# GasSensorModule_v2_0.net
KiCad netlist of a schematic drawn in EAGLE
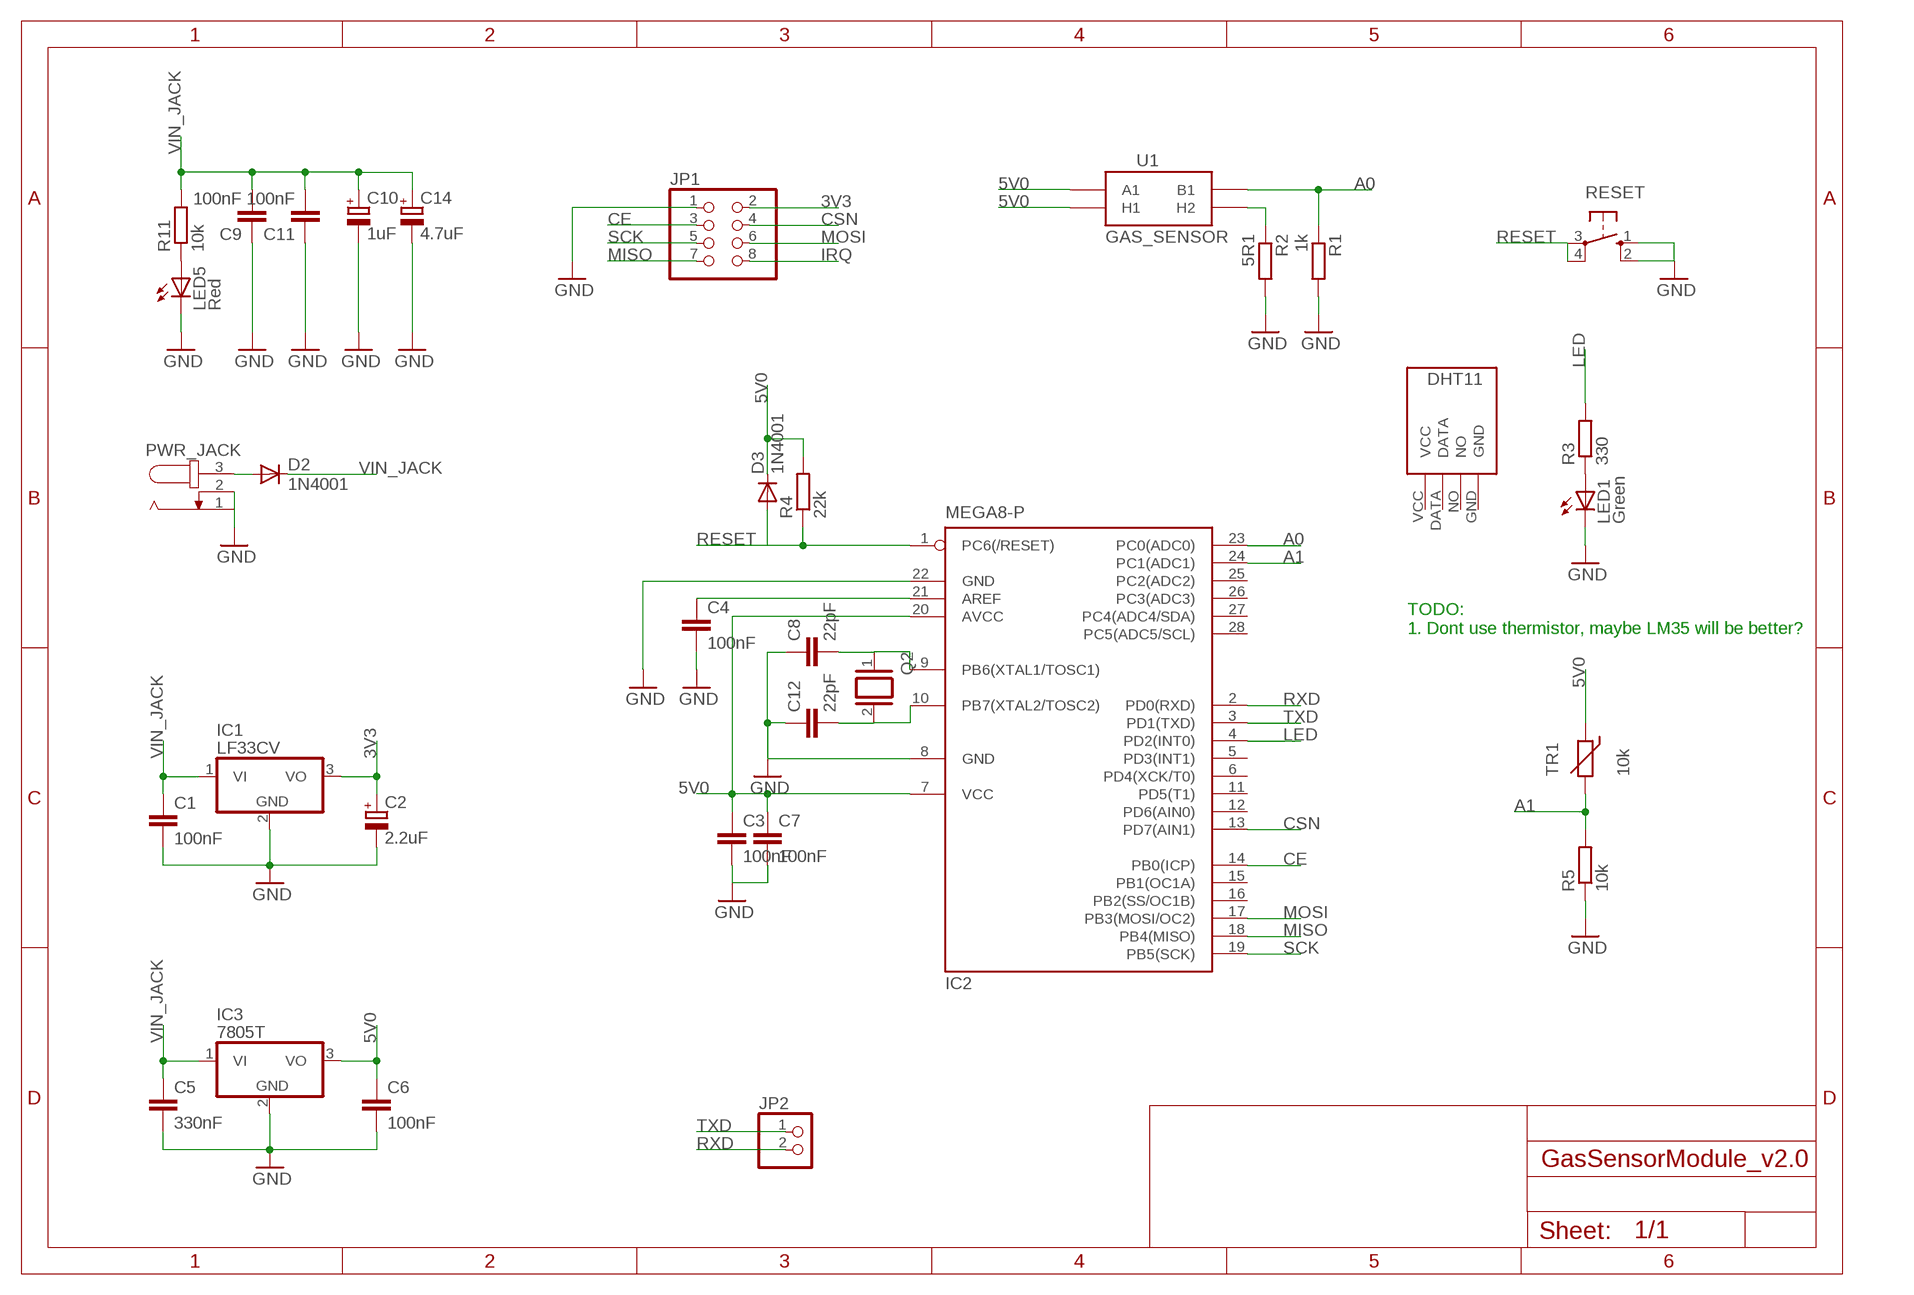
[diagram p0: schematic, sheet 1]

(export (version "E")
  (design (tool "Eeschema 10.0.6"))
  (components
    (comp (ref "C1")
      (value "100nF")
      (footprint "eagle-import:C025-025X050")
      (libsource (lib "eagle-import") (part "C-EU025-025X050"))
    )
    (comp (ref "C2")
      (value "2.2uF")
      (footprint "eagle-import:E2,5-5")
      (libsource (lib "eagle-import") (part "CPOL-EUE2.5-5"))
    )
    (comp (ref "C3")
      (value "100nF")
      (footprint "eagle-import:C025-025X050")
      (libsource (lib "eagle-import") (part "C-EU025-025X050"))
    )
    (comp (ref "C4")
      (value "100nF")
      (footprint "eagle-import:C025-025X050")
      (libsource (lib "eagle-import") (part "C-EU025-025X050"))
    )
    (comp (ref "C5")
      (value "330nF")
      (footprint "eagle-import:C025-025X050")
      (libsource (lib "eagle-import") (part "C-EU025-025X050"))
    )
    (comp (ref "C6")
      (value "100nF")
      (footprint "eagle-import:C025-025X050")
      (libsource (lib "eagle-import") (part "C-EU025-025X050"))
    )
    (comp (ref "C7")
      (value "100nF")
      (footprint "eagle-import:C025-025X050")
      (libsource (lib "eagle-import") (part "C-EU025-025X050"))
    )
    (comp (ref "C8")
      (value "22pF")
      (footprint "eagle-import:C025-025X050")
      (libsource (lib "eagle-import") (part "C-EU025-025X050"))
    )
    (comp (ref "C9")
      (value "100nF")
      (footprint "eagle-import:C025-025X050")
      (libsource (lib "eagle-import") (part "C-EU025-025X050"))
    )
    (comp (ref "C10")
      (value "1uF")
      (footprint "eagle-import:E2,5-5")
      (libsource (lib "eagle-import") (part "CPOL-EUE2.5-5"))
    )
    (comp (ref "C11")
      (value "100nF")
      (footprint "eagle-import:C025-025X050")
      (libsource (lib "eagle-import") (part "C-EU025-025X050"))
    )
    (comp (ref "C12")
      (value "22pF")
      (footprint "eagle-import:C025-025X050")
      (libsource (lib "eagle-import") (part "C-EU025-025X050"))
    )
    (comp (ref "C14")
      (value "4.7uF")
      (footprint "eagle-import:E2,5-5")
      (libsource (lib "eagle-import") (part "CPOL-EUE2.5-5"))
    )
    (comp (ref "D2")
      (value "1N4001")
      (footprint "eagle-import:DO41-10")
      (libsource (lib "eagle-import") (part "1N4004"))
    )
    (comp (ref "D3")
      (value "1N4001")
      (footprint "eagle-import:DO41-10")
      (libsource (lib "eagle-import") (part "1N4004"))
    )
    (comp (ref "IC1")
      (value "LF33CV")
      (footprint "eagle-import:TO220H")
      (libsource (lib "eagle-import") (part "78T05"))
    )
    (comp (ref "IC2")
      (value "MEGA8-P")
      (footprint "eagle-import:DIL28-3")
      (libsource (lib "eagle-import") (part "MEGA8-P"))
    )
    (comp (ref "IC3")
      (value "7805T")
      (footprint "eagle-import:TO220H")
      (libsource (lib "eagle-import") (part "78T05"))
    )
    (comp (ref "JP1")
      (value "PINHD-2X4")
      (footprint "eagle-import:2X04")
      (libsource (lib "eagle-import") (part "PINHD-2X4"))
    )
    (comp (ref "JP2")
      (value "PINHD-1X2/90")
      (footprint "eagle-import:1X02_90")
      (libsource (lib "eagle-import") (part "PINHD-1X2/90"))
    )
    (comp (ref "LED1")
      (value "Green")
      (footprint "eagle-import:LED3MM")
      (libsource (lib "eagle-import") (part "LED3MM"))
    )
    (comp (ref "LED5")
      (value "Red")
      (footprint "eagle-import:LED3MM")
      (libsource (lib "eagle-import") (part "LED3MM"))
    )
    (comp (ref "PWR_JACK")
      (value "JACK-PLUG0")
      (footprint "eagle-import:SPC4077")
      (libsource (lib "eagle-import") (part "JACK-PLUG0"))
    )
    (comp (ref "Q2")
      (value "XTAL/S")
      (footprint "eagle-import:QS")
      (libsource (lib "eagle-import") (part "XTAL/S"))
    )
    (comp (ref "R1")
      (value "1k")
      (footprint "eagle-import:0207_10")
      (libsource (lib "eagle-import") (part "R-EU_0207/10"))
    )
    (comp (ref "R2")
      (value "5R1")
      (footprint "eagle-import:0207_10")
      (libsource (lib "eagle-import") (part "R-EU_0207/10"))
    )
    (comp (ref "R3")
      (value "330")
      (footprint "eagle-import:0207_10")
      (libsource (lib "eagle-import") (part "R-EU_0207/10"))
    )
    (comp (ref "R4")
      (value "22k")
      (footprint "eagle-import:0207_10")
      (libsource (lib "eagle-import") (part "R-EU_0207/10"))
    )
    (comp (ref "R5")
      (value "10k")
      (footprint "eagle-import:0207_10")
      (libsource (lib "eagle-import") (part "R-EU_0207/10"))
    )
    (comp (ref "R11")
      (value "10k")
      (footprint "eagle-import:0207_10")
      (libsource (lib "eagle-import") (part "R-EU_0207/10"))
    )
    (comp (ref "RESET")
      (value "10-XX")
      (footprint "eagle-import:B3F-10XX")
      (fields (field (name "MPN") "B3F-1000"))
      (libsource (lib "eagle-import") (part "10-XX"))
    )
    (comp (ref "TR1")
      (value "10k")
      (footprint "eagle-import:RS-2,5")
      (libsource (lib "eagle-import") (part "THERMISTOR_R-2,5"))
    )
    (comp (ref "U$1")
      (value "DHT11-PION.")
      (footprint "eagle-import:DHT11-PION.")
      (libsource (lib "eagle-import") (part "DHT11-PION."))
    )
    (comp (ref "U1")
      (value "GAS_SENSOR")
      (footprint "eagle-import:MQ-3")
      (libsource (lib "eagle-import") (part "GAS_SENSOR"))
    )
  )
  (nets
    (net (code "1") (name "/3V3") (class "Default")
      (node (ref "C2") (pin "+") (pinfunction "+_+") (pintype "passive"))
      (node (ref "IC1") (pin "3") (pinfunction "VO_3") (pintype "passive"))
      (node (ref "JP1") (pin "2") (pinfunction "2_2") (pintype "passive"))
    )
    (net (code "2") (name "/5V0") (class "Default")
      (node (ref "C3") (pin "1") (pinfunction "1_1") (pintype "passive"))
      (node (ref "C6") (pin "1") (pinfunction "1_1") (pintype "passive"))
      (node (ref "C7") (pin "1") (pinfunction "1_1") (pintype "passive"))
      (node (ref "D3") (pin "C") (pinfunction "C_C") (pintype "passive"))
      (node (ref "IC2") (pin "20") (pinfunction "AVCC_20") (pintype "power_in"))
      (node (ref "IC2") (pin "7") (pinfunction "VCC_7") (pintype "power_in"))
      (node (ref "IC3") (pin "3") (pinfunction "VO_3") (pintype "passive"))
      (node (ref "R4") (pin "2") (pinfunction "2_2") (pintype "passive"))
      (node (ref "TR1") (pin "1") (pinfunction "1_1") (pintype "passive"))
      (node (ref "U1") (pin "A1") (pinfunction "A1_A1") (pintype "bidirectional"))
      (node (ref "U1") (pin "HA") (pinfunction "H1_HA") (pintype "bidirectional"))
    )
    (net (code "3") (name "/A0") (class "Default")
      (node (ref "IC2") (pin "23") (pinfunction "PC0(ADC0)_23") (pintype "bidirectional"))
      (node (ref "R1") (pin "1") (pinfunction "1_1") (pintype "passive"))
      (node (ref "U1") (pin "B1") (pinfunction "B1_B1") (pintype "bidirectional"))
    )
    (net (code "4") (name "/A1") (class "Default")
      (node (ref "IC2") (pin "24") (pinfunction "PC1(ADC1)_24") (pintype "bidirectional"))
      (node (ref "R5") (pin "2") (pinfunction "2_2") (pintype "passive"))
      (node (ref "TR1") (pin "2") (pinfunction "2_2") (pintype "passive"))
    )
    (net (code "5") (name "/CE") (class "Default")
      (node (ref "IC2") (pin "14") (pinfunction "PB0(ICP)_14") (pintype "bidirectional"))
      (node (ref "JP1") (pin "3") (pinfunction "3_3") (pintype "passive"))
    )
    (net (code "6") (name "/CSN") (class "Default")
      (node (ref "IC2") (pin "13") (pinfunction "PD7(AIN1)_13") (pintype "bidirectional"))
      (node (ref "JP1") (pin "4") (pinfunction "4_4") (pintype "passive"))
    )
    (net (code "7") (name "/IRQ") (class "Default")
      (node (ref "JP1") (pin "8") (pinfunction "8_8") (pintype "passive"))
    )
    (net (code "8") (name "/LED") (class "Default")
      (node (ref "IC2") (pin "4") (pinfunction "PD2(INT0)_4") (pintype "bidirectional"))
      (node (ref "R3") (pin "2") (pinfunction "2_2") (pintype "passive"))
    )
    (net (code "9") (name "/MISO") (class "Default")
      (node (ref "IC2") (pin "18") (pinfunction "PB4(MISO)_18") (pintype "bidirectional"))
      (node (ref "JP1") (pin "7") (pinfunction "7_7") (pintype "passive"))
    )
    (net (code "10") (name "/MOSI") (class "Default")
      (node (ref "IC2") (pin "17") (pinfunction "PB3(MOSI/OC2)_17") (pintype "bidirectional"))
      (node (ref "JP1") (pin "6") (pinfunction "6_6") (pintype "passive"))
    )
    (net (code "11") (name "/RESET") (class "Default")
      (node (ref "D3") (pin "A") (pinfunction "A_A") (pintype "passive"))
      (node (ref "IC2") (pin "1") (pinfunction "PC6(/RESET)_1") (pintype "bidirectional"))
      (node (ref "R4") (pin "1") (pinfunction "1_1") (pintype "passive"))
      (node (ref "RESET") (pin "3") (pinfunction "P_3") (pintype "passive"))
      (node (ref "RESET") (pin "4") (pinfunction "P1_4") (pintype "passive"))
    )
    (net (code "12") (name "/RXD") (class "Default")
      (node (ref "IC2") (pin "2") (pinfunction "PD0(RXD)_2") (pintype "bidirectional"))
      (node (ref "JP2") (pin "2") (pinfunction "2_2") (pintype "passive"))
    )
    (net (code "13") (name "/SCK") (class "Default")
      (node (ref "IC2") (pin "19") (pinfunction "PB5(SCK)_19") (pintype "bidirectional"))
      (node (ref "JP1") (pin "5") (pinfunction "5_5") (pintype "passive"))
    )
    (net (code "14") (name "/TXD") (class "Default")
      (node (ref "IC2") (pin "3") (pinfunction "PD1(TXD)_3") (pintype "bidirectional"))
      (node (ref "JP2") (pin "1") (pinfunction "1_1") (pintype "passive"))
    )
    (net (code "15") (name "/VIN_JACK") (class "Default")
      (node (ref "C1") (pin "1") (pinfunction "1_1") (pintype "passive"))
      (node (ref "C10") (pin "+") (pinfunction "+_+") (pintype "passive"))
      (node (ref "C11") (pin "2") (pinfunction "2_2") (pintype "passive"))
      (node (ref "C14") (pin "+") (pinfunction "+_+") (pintype "passive"))
      (node (ref "C5") (pin "1") (pinfunction "1_1") (pintype "passive"))
      (node (ref "C9") (pin "2") (pinfunction "2_2") (pintype "passive"))
      (node (ref "D2") (pin "C") (pinfunction "C_C") (pintype "passive"))
      (node (ref "IC1") (pin "1") (pinfunction "VI_1") (pintype "input"))
      (node (ref "IC3") (pin "1") (pinfunction "VI_1") (pintype "input"))
      (node (ref "R11") (pin "2") (pinfunction "2_2") (pintype "passive"))
    )
    (net (code "16") (name "GND") (class "Default")
      (node (ref "C1") (pin "2") (pinfunction "2_2") (pintype "passive"))
      (node (ref "C10") (pin "-") (pinfunction "-_-") (pintype "passive"))
      (node (ref "C11") (pin "1") (pinfunction "1_1") (pintype "passive"))
      (node (ref "C12") (pin "1") (pinfunction "1_1") (pintype "passive"))
      (node (ref "C14") (pin "-") (pinfunction "-_-") (pintype "passive"))
      (node (ref "C2") (pin "-") (pinfunction "-_-") (pintype "passive"))
      (node (ref "C3") (pin "2") (pinfunction "2_2") (pintype "passive"))
      (node (ref "C4") (pin "2") (pinfunction "2_2") (pintype "passive"))
      (node (ref "C5") (pin "2") (pinfunction "2_2") (pintype "passive"))
      (node (ref "C6") (pin "2") (pinfunction "2_2") (pintype "passive"))
      (node (ref "C7") (pin "2") (pinfunction "2_2") (pintype "passive"))
      (node (ref "C8") (pin "1") (pinfunction "1_1") (pintype "passive"))
      (node (ref "C9") (pin "1") (pinfunction "1_1") (pintype "passive"))
      (node (ref "IC1") (pin "2") (pinfunction "GND_2") (pintype "passive"))
      (node (ref "IC2") (pin "22") (pinfunction "GND_22") (pintype "power_in"))
      (node (ref "IC2") (pin "8") (pinfunction "GND_8") (pintype "power_in"))
      (node (ref "IC3") (pin "2") (pinfunction "GND_2") (pintype "passive"))
      (node (ref "JP1") (pin "1") (pinfunction "1_1") (pintype "passive"))
      (node (ref "LED1") (pin "K") (pinfunction "C_K") (pintype "passive"))
      (node (ref "LED5") (pin "K") (pinfunction "C_K") (pintype "passive"))
      (node (ref "PWR_JACK") (pin "1") (pinfunction "1_1") (pintype "passive"))
      (node (ref "PWR_JACK") (pin "2") (pinfunction "2_2") (pintype "passive"))
      (node (ref "R1") (pin "2") (pinfunction "2_2") (pintype "passive"))
      (node (ref "R2") (pin "2") (pinfunction "2_2") (pintype "passive"))
      (node (ref "R5") (pin "1") (pinfunction "1_1") (pintype "passive"))
      (node (ref "RESET") (pin "1") (pinfunction "S_1") (pintype "passive"))
      (node (ref "RESET") (pin "2") (pinfunction "S1_2") (pintype "passive"))
    )
    (net (code "17") (name "Net-(D2-PadA)") (class "Default")
      (node (ref "D2") (pin "A") (pinfunction "A_A") (pintype "passive"))
      (node (ref "PWR_JACK") (pin "3") (pinfunction "3_3") (pintype "passive"))
    )
    (net (code "18") (name "Net-(IC2-AREF)") (class "Default")
      (node (ref "C4") (pin "1") (pinfunction "1_1") (pintype "passive"))
      (node (ref "IC2") (pin "21") (pinfunction "AREF_21") (pintype "passive"))
    )
    (net (code "19") (name "Net-(IC2-PB6(XTAL1{slash}TOSC1))") (class "Default")
      (node (ref "C8") (pin "2") (pinfunction "2_2") (pintype "passive"))
      (node (ref "IC2") (pin "9") (pinfunction "PB6(XTAL1/TOSC1)_9") (pintype "bidirectional"))
      (node (ref "Q2") (pin "1") (pinfunction "1_1") (pintype "passive"))
    )
    (net (code "20") (name "Net-(IC2-PB7(XTAL2{slash}TOSC2))") (class "Default")
      (node (ref "C12") (pin "2") (pinfunction "2_2") (pintype "passive"))
      (node (ref "IC2") (pin "10") (pinfunction "PB7(XTAL2/TOSC2)_10") (pintype "bidirectional"))
      (node (ref "Q2") (pin "2") (pinfunction "2_2") (pintype "passive"))
    )
    (net (code "21") (name "Net-(LED1-PadA)") (class "Default")
      (node (ref "LED1") (pin "A") (pinfunction "A_A") (pintype "passive"))
      (node (ref "R3") (pin "1") (pinfunction "1_1") (pintype "passive"))
    )
    (net (code "22") (name "Net-(LED5-PadA)") (class "Default")
      (node (ref "LED5") (pin "A") (pinfunction "A_A") (pintype "passive"))
      (node (ref "R11") (pin "1") (pinfunction "1_1") (pintype "passive"))
    )
    (net (code "23") (name "Net-(U1-H2)") (class "Default")
      (node (ref "R2") (pin "1") (pinfunction "1_1") (pintype "passive"))
      (node (ref "U1") (pin "HB") (pinfunction "H2_HB") (pintype "bidirectional"))
    )
    (net (code "24") (name "unconnected-(IC2-PB1(OC1A)-Pad15)") (class "Default")
      (node (ref "IC2") (pin "15") (pinfunction "PB1(OC1A)_15") (pintype "bidirectional"))
    )
    (net (code "25") (name "unconnected-(IC2-PB2(SS{slash}OC1B)-Pad16)") (class "Default")
      (node (ref "IC2") (pin "16") (pinfunction "PB2(SS/OC1B)_16") (pintype "bidirectional"))
    )
    (net (code "26") (name "unconnected-(IC2-PC2(ADC2)-Pad25)") (class "Default")
      (node (ref "IC2") (pin "25") (pinfunction "PC2(ADC2)_25") (pintype "bidirectional"))
    )
    (net (code "27") (name "unconnected-(IC2-PC3(ADC3)-Pad26)") (class "Default")
      (node (ref "IC2") (pin "26") (pinfunction "PC3(ADC3)_26") (pintype "bidirectional"))
    )
    (net (code "28") (name "unconnected-(IC2-PC4(ADC4{slash}SDA)-Pad27)") (class "Default")
      (node (ref "IC2") (pin "27") (pinfunction "PC4(ADC4/SDA)_27") (pintype "bidirectional"))
    )
    (net (code "29") (name "unconnected-(IC2-PC5(ADC5{slash}SCL)-Pad28)") (class "Default")
      (node (ref "IC2") (pin "28") (pinfunction "PC5(ADC5/SCL)_28") (pintype "bidirectional"))
    )
    (net (code "30") (name "unconnected-(IC2-PD3(INT1)-Pad5)") (class "Default")
      (node (ref "IC2") (pin "5") (pinfunction "PD3(INT1)_5") (pintype "bidirectional"))
    )
    (net (code "31") (name "unconnected-(IC2-PD4(XCK{slash}T0)-Pad6)") (class "Default")
      (node (ref "IC2") (pin "6") (pinfunction "PD4(XCK/T0)_6") (pintype "bidirectional"))
    )
    (net (code "32") (name "unconnected-(IC2-PD5(T1)-Pad11)") (class "Default")
      (node (ref "IC2") (pin "11") (pinfunction "PD5(T1)_11") (pintype "bidirectional"))
    )
    (net (code "33") (name "unconnected-(IC2-PD6(AIN0)-Pad12)") (class "Default")
      (node (ref "IC2") (pin "12") (pinfunction "PD6(AIN0)_12") (pintype "bidirectional"))
    )
    (net (code "34") (name "unconnected-(U$1-PadDATA)") (class "Default")
      (node (ref "U$1") (pin "DATA") (pinfunction "DATA_DATA") (pintype "bidirectional"))
    )
    (net (code "35") (name "unconnected-(U$1-PadGND)") (class "Default")
      (node (ref "U$1") (pin "GND") (pinfunction "GND_GND") (pintype "bidirectional"))
    )
    (net (code "36") (name "unconnected-(U$1-PadNO)") (class "Default")
      (node (ref "U$1") (pin "NO") (pinfunction "NO_NO") (pintype "bidirectional"))
    )
    (net (code "37") (name "unconnected-(U$1-PadVCC)") (class "Default")
      (node (ref "U$1") (pin "VCC") (pinfunction "VCC_VCC") (pintype "bidirectional"))
    )
  )
)
